# Nucleo.net
KiCad netlist of a schematic drawn in Altium Designer
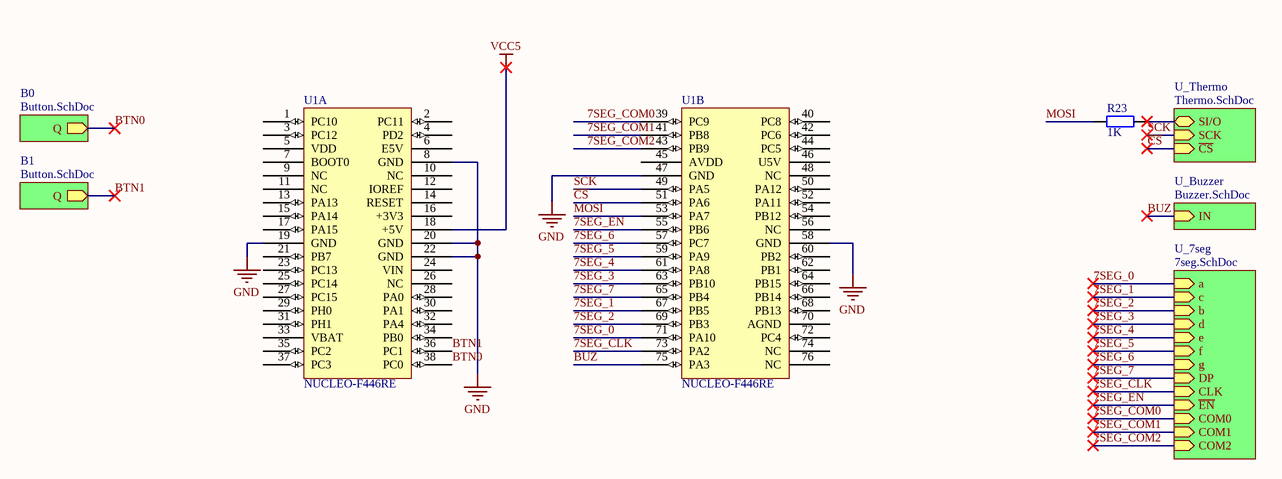
[diagram p0: Nucleo.SchDoc]

(export (version "E")
  (design (tool "Eeschema 10.0.6"))
  (components
    (comp (ref "R23")
      (value "1K")
      (footprint "FP_0805_RES")
      (description "Resistor")
      (fields (field (name "TOLERANCE") "5%") (field (name "POWER") "125mW"))
      (libsource (lib "hallglib") (part "RES 1K"))
    )
    (comp (ref "U1")
      (value "NUCLEO-F446RE")
      (footprint "FP_NUCLEO-64")
      (libsource (lib "hallglib") (part "NUCLEO-F446RE"))
    )
  )
  (nets
    (net (code "1") (name "/7SEG_0") (class "Default")
      (node (ref "U1") (pin "71") (pinfunction "PA10_71") (pintype "bidirectional+no_connect"))
    )
    (net (code "2") (name "/7SEG_1") (class "Default")
      (node (ref "U1") (pin "67") (pinfunction "PB5_67") (pintype "bidirectional+no_connect"))
    )
    (net (code "3") (name "/7SEG_2") (class "Default")
      (node (ref "U1") (pin "69") (pinfunction "PB3_69") (pintype "bidirectional+no_connect"))
    )
    (net (code "4") (name "/7SEG_3") (class "Default")
      (node (ref "U1") (pin "63") (pinfunction "PB10_63") (pintype "bidirectional+no_connect"))
    )
    (net (code "5") (name "/7SEG_4") (class "Default")
      (node (ref "U1") (pin "61") (pinfunction "PA8_61") (pintype "bidirectional+no_connect"))
    )
    (net (code "6") (name "/7SEG_5") (class "Default")
      (node (ref "U1") (pin "59") (pinfunction "PA9_59") (pintype "bidirectional+no_connect"))
    )
    (net (code "7") (name "/7SEG_6") (class "Default")
      (node (ref "U1") (pin "57") (pinfunction "PC7_57") (pintype "bidirectional+no_connect"))
    )
    (net (code "8") (name "/7SEG_7") (class "Default")
      (node (ref "U1") (pin "65") (pinfunction "PB4_65") (pintype "bidirectional+no_connect"))
    )
    (net (code "9") (name "/7SEG_CLK") (class "Default")
      (node (ref "U1") (pin "73") (pinfunction "PA2_73") (pintype "bidirectional+no_connect"))
    )
    (net (code "10") (name "/7SEG_COM0") (class "Default")
      (node (ref "U1") (pin "39") (pinfunction "PC9_39") (pintype "bidirectional+no_connect"))
    )
    (net (code "11") (name "/7SEG_COM1") (class "Default")
      (node (ref "U1") (pin "41") (pinfunction "PB8_41") (pintype "bidirectional+no_connect"))
    )
    (net (code "12") (name "/7SEG_COM2") (class "Default")
      (node (ref "U1") (pin "43") (pinfunction "PB9_43") (pintype "bidirectional+no_connect"))
    )
    (net (code "13") (name "/7SEG_EN") (class "Default")
      (node (ref "U1") (pin "55") (pinfunction "PB6_55") (pintype "bidirectional+no_connect"))
    )
    (net (code "14") (name "/BTN0") (class "Default")
      (node (ref "U1") (pin "38") (pinfunction "PC0_38") (pintype "bidirectional"))
    )
    (net (code "15") (name "/BTN1") (class "Default")
      (node (ref "U1") (pin "36") (pinfunction "PC1_36") (pintype "bidirectional+no_connect"))
    )
    (net (code "16") (name "/BUZ") (class "Default")
      (node (ref "U1") (pin "75") (pinfunction "PA3_75") (pintype "bidirectional"))
    )
    (net (code "17") (name "/MOSI") (class "Default")
      (node (ref "R23") (pin "1") (pinfunction "1_1") (pintype "passive"))
      (node (ref "U1") (pin "53") (pinfunction "PA7_53") (pintype "bidirectional"))
    )
    (net (code "18") (name "/SCK") (class "Default")
      (node (ref "U1") (pin "49") (pinfunction "PA5_49") (pintype "bidirectional"))
    )
    (net (code "19") (name "/SI{slash}O") (class "Default")
      (node (ref "R23") (pin "2") (pinfunction "2_2") (pintype "passive+no_connect"))
    )
    (net (code "20") (name "/~{CS}") (class "Default")
      (node (ref "U1") (pin "51") (pinfunction "PA6_51") (pintype "bidirectional"))
    )
    (net (code "21") (name "GND") (class "Default")
      (node (ref "U1") (pin "19") (pinfunction "GND_19") (pintype "passive"))
      (node (ref "U1") (pin "20") (pinfunction "GND_20") (pintype "passive"))
      (node (ref "U1") (pin "22") (pinfunction "GND_22") (pintype "passive"))
      (node (ref "U1") (pin "47") (pinfunction "GND_47") (pintype "passive"))
      (node (ref "U1") (pin "58") (pinfunction "GND_58") (pintype "passive"))
      (node (ref "U1") (pin "8") (pinfunction "GND_8") (pintype "passive"))
    )
    (net (code "22") (name "VCC5") (class "Default")
      (node (ref "U1") (pin "18") (pinfunction "+5V_18") (pintype "power_in"))
    )
    (net (code "23") (name "unconnected-(U1A-+3V3-Pad16)") (class "Default")
      (node (ref "U1") (pin "16") (pinfunction "+3V3_16") (pintype "power_in"))
    )
    (net (code "24") (name "unconnected-(U1A-BOOT0-Pad7)") (class "Default")
      (node (ref "U1") (pin "7") (pinfunction "BOOT0_7") (pintype "passive"))
    )
    (net (code "25") (name "unconnected-(U1A-E5V-Pad6)") (class "Default")
      (node (ref "U1") (pin "6") (pinfunction "E5V_6") (pintype "power_in"))
    )
    (net (code "26") (name "unconnected-(U1A-IOREF-Pad12)") (class "Default")
      (node (ref "U1") (pin "12") (pinfunction "IOREF_12") (pintype "passive"))
    )
    (net (code "27") (name "unconnected-(U1A-NC-Pad9)") (class "Default")
      (node (ref "U1") (pin "9") (pinfunction "NC_9") (pintype "passive"))
    )
    (net (code "28") (name "unconnected-(U1A-NC-Pad10)") (class "Default")
      (node (ref "U1") (pin "10") (pinfunction "NC_10") (pintype "passive"))
    )
    (net (code "29") (name "unconnected-(U1A-NC-Pad11)") (class "Default")
      (node (ref "U1") (pin "11") (pinfunction "NC_11") (pintype "passive"))
    )
    (net (code "30") (name "unconnected-(U1A-NC-Pad26)") (class "Default")
      (node (ref "U1") (pin "26") (pinfunction "NC_26") (pintype "passive"))
    )
    (net (code "31") (name "unconnected-(U1A-PA0-Pad28)") (class "Default")
      (node (ref "U1") (pin "28") (pinfunction "PA0_28") (pintype "bidirectional"))
    )
    (net (code "32") (name "unconnected-(U1A-PA1-Pad30)") (class "Default")
      (node (ref "U1") (pin "30") (pinfunction "PA1_30") (pintype "bidirectional"))
    )
    (net (code "33") (name "unconnected-(U1A-PA4-Pad32)") (class "Default")
      (node (ref "U1") (pin "32") (pinfunction "PA4_32") (pintype "bidirectional"))
    )
    (net (code "34") (name "unconnected-(U1A-PA13-Pad13)") (class "Default")
      (node (ref "U1") (pin "13") (pinfunction "PA13_13") (pintype "bidirectional"))
    )
    (net (code "35") (name "unconnected-(U1A-PA14-Pad15)") (class "Default")
      (node (ref "U1") (pin "15") (pinfunction "PA14_15") (pintype "bidirectional"))
    )
    (net (code "36") (name "unconnected-(U1A-PA15-Pad17)") (class "Default")
      (node (ref "U1") (pin "17") (pinfunction "PA15_17") (pintype "bidirectional"))
    )
    (net (code "37") (name "unconnected-(U1A-PB0-Pad34)") (class "Default")
      (node (ref "U1") (pin "34") (pinfunction "PB0_34") (pintype "bidirectional"))
    )
    (net (code "38") (name "unconnected-(U1A-PB7-Pad21)") (class "Default")
      (node (ref "U1") (pin "21") (pinfunction "PB7_21") (pintype "bidirectional"))
    )
    (net (code "39") (name "unconnected-(U1A-PC2-Pad35)") (class "Default")
      (node (ref "U1") (pin "35") (pinfunction "PC2_35") (pintype "bidirectional"))
    )
    (net (code "40") (name "unconnected-(U1A-PC3-Pad37)") (class "Default")
      (node (ref "U1") (pin "37") (pinfunction "PC3_37") (pintype "bidirectional"))
    )
    (net (code "41") (name "unconnected-(U1A-PC10-Pad1)") (class "Default")
      (node (ref "U1") (pin "1") (pinfunction "PC10_1") (pintype "bidirectional"))
    )
    (net (code "42") (name "unconnected-(U1A-PC11-Pad2)") (class "Default")
      (node (ref "U1") (pin "2") (pinfunction "PC11_2") (pintype "bidirectional"))
    )
    (net (code "43") (name "unconnected-(U1A-PC12-Pad3)") (class "Default")
      (node (ref "U1") (pin "3") (pinfunction "PC12_3") (pintype "bidirectional"))
    )
    (net (code "44") (name "unconnected-(U1A-PC13-Pad23)") (class "Default")
      (node (ref "U1") (pin "23") (pinfunction "PC13_23") (pintype "bidirectional"))
    )
    (net (code "45") (name "unconnected-(U1A-PC14-Pad25)") (class "Default")
      (node (ref "U1") (pin "25") (pinfunction "PC14_25") (pintype "bidirectional"))
    )
    (net (code "46") (name "unconnected-(U1A-PC15-Pad27)") (class "Default")
      (node (ref "U1") (pin "27") (pinfunction "PC15_27") (pintype "bidirectional"))
    )
    (net (code "47") (name "unconnected-(U1A-PD2-Pad4)") (class "Default")
      (node (ref "U1") (pin "4") (pinfunction "PD2_4") (pintype "bidirectional"))
    )
    (net (code "48") (name "unconnected-(U1A-PH0-Pad29)") (class "Default")
      (node (ref "U1") (pin "29") (pinfunction "PH0_29") (pintype "bidirectional"))
    )
    (net (code "49") (name "unconnected-(U1A-PH1-Pad31)") (class "Default")
      (node (ref "U1") (pin "31") (pinfunction "PH1_31") (pintype "bidirectional"))
    )
    (net (code "50") (name "unconnected-(U1A-RESET-Pad14)") (class "Default")
      (node (ref "U1") (pin "14") (pinfunction "RESET_14") (pintype "passive"))
    )
    (net (code "51") (name "unconnected-(U1A-VBAT-Pad33)") (class "Default")
      (node (ref "U1") (pin "33") (pinfunction "VBAT_33") (pintype "power_in"))
    )
    (net (code "52") (name "unconnected-(U1A-VDD-Pad5)") (class "Default")
      (node (ref "U1") (pin "5") (pinfunction "VDD_5") (pintype "power_in"))
    )
    (net (code "53") (name "unconnected-(U1A-VIN-Pad24)") (class "Default")
      (node (ref "U1") (pin "24") (pinfunction "VIN_24") (pintype "power_in"))
    )
    (net (code "54") (name "unconnected-(U1B-AGND-Pad70)") (class "Default")
      (node (ref "U1") (pin "70") (pinfunction "AGND_70") (pintype "passive"))
    )
    (net (code "55") (name "unconnected-(U1B-AVDD-Pad45)") (class "Default")
      (node (ref "U1") (pin "45") (pinfunction "AVDD_45") (pintype "power_in"))
    )
    (net (code "56") (name "unconnected-(U1B-NC-Pad48)") (class "Default")
      (node (ref "U1") (pin "48") (pinfunction "NC_48") (pintype "passive"))
    )
    (net (code "57") (name "unconnected-(U1B-NC-Pad56)") (class "Default")
      (node (ref "U1") (pin "56") (pinfunction "NC_56") (pintype "passive"))
    )
    (net (code "58") (name "unconnected-(U1B-NC-Pad74)") (class "Default")
      (node (ref "U1") (pin "74") (pinfunction "NC_74") (pintype "passive"))
    )
    (net (code "59") (name "unconnected-(U1B-NC-Pad76)") (class "Default")
      (node (ref "U1") (pin "76") (pinfunction "NC_76") (pintype "passive"))
    )
    (net (code "60") (name "unconnected-(U1B-PA11-Pad52)") (class "Default")
      (node (ref "U1") (pin "52") (pinfunction "PA11_52") (pintype "bidirectional"))
    )
    (net (code "61") (name "unconnected-(U1B-PA12-Pad50)") (class "Default")
      (node (ref "U1") (pin "50") (pinfunction "PA12_50") (pintype "bidirectional"))
    )
    (net (code "62") (name "unconnected-(U1B-PB1-Pad62)") (class "Default")
      (node (ref "U1") (pin "62") (pinfunction "PB1_62") (pintype "bidirectional"))
    )
    (net (code "63") (name "unconnected-(U1B-PB2-Pad60)") (class "Default")
      (node (ref "U1") (pin "60") (pinfunction "PB2_60") (pintype "bidirectional"))
    )
    (net (code "64") (name "unconnected-(U1B-PB12-Pad54)") (class "Default")
      (node (ref "U1") (pin "54") (pinfunction "PB12_54") (pintype "bidirectional"))
    )
    (net (code "65") (name "unconnected-(U1B-PB13-Pad68)") (class "Default")
      (node (ref "U1") (pin "68") (pinfunction "PB13_68") (pintype "bidirectional"))
    )
    (net (code "66") (name "unconnected-(U1B-PB14-Pad66)") (class "Default")
      (node (ref "U1") (pin "66") (pinfunction "PB14_66") (pintype "bidirectional"))
    )
    (net (code "67") (name "unconnected-(U1B-PB15-Pad64)") (class "Default")
      (node (ref "U1") (pin "64") (pinfunction "PB15_64") (pintype "bidirectional"))
    )
    (net (code "68") (name "unconnected-(U1B-PC4-Pad72)") (class "Default")
      (node (ref "U1") (pin "72") (pinfunction "PC4_72") (pintype "bidirectional"))
    )
    (net (code "69") (name "unconnected-(U1B-PC5-Pad44)") (class "Default")
      (node (ref "U1") (pin "44") (pinfunction "PC5_44") (pintype "bidirectional"))
    )
    (net (code "70") (name "unconnected-(U1B-PC6-Pad42)") (class "Default")
      (node (ref "U1") (pin "42") (pinfunction "PC6_42") (pintype "bidirectional"))
    )
    (net (code "71") (name "unconnected-(U1B-PC8-Pad40)") (class "Default")
      (node (ref "U1") (pin "40") (pinfunction "PC8_40") (pintype "bidirectional"))
    )
    (net (code "72") (name "unconnected-(U1B-U5V-Pad46)") (class "Default")
      (node (ref "U1") (pin "46") (pinfunction "U5V_46") (pintype "power_in"))
    )
  )
)
